# power.net
KiCad netlist of a schematic drawn in Altium Designer
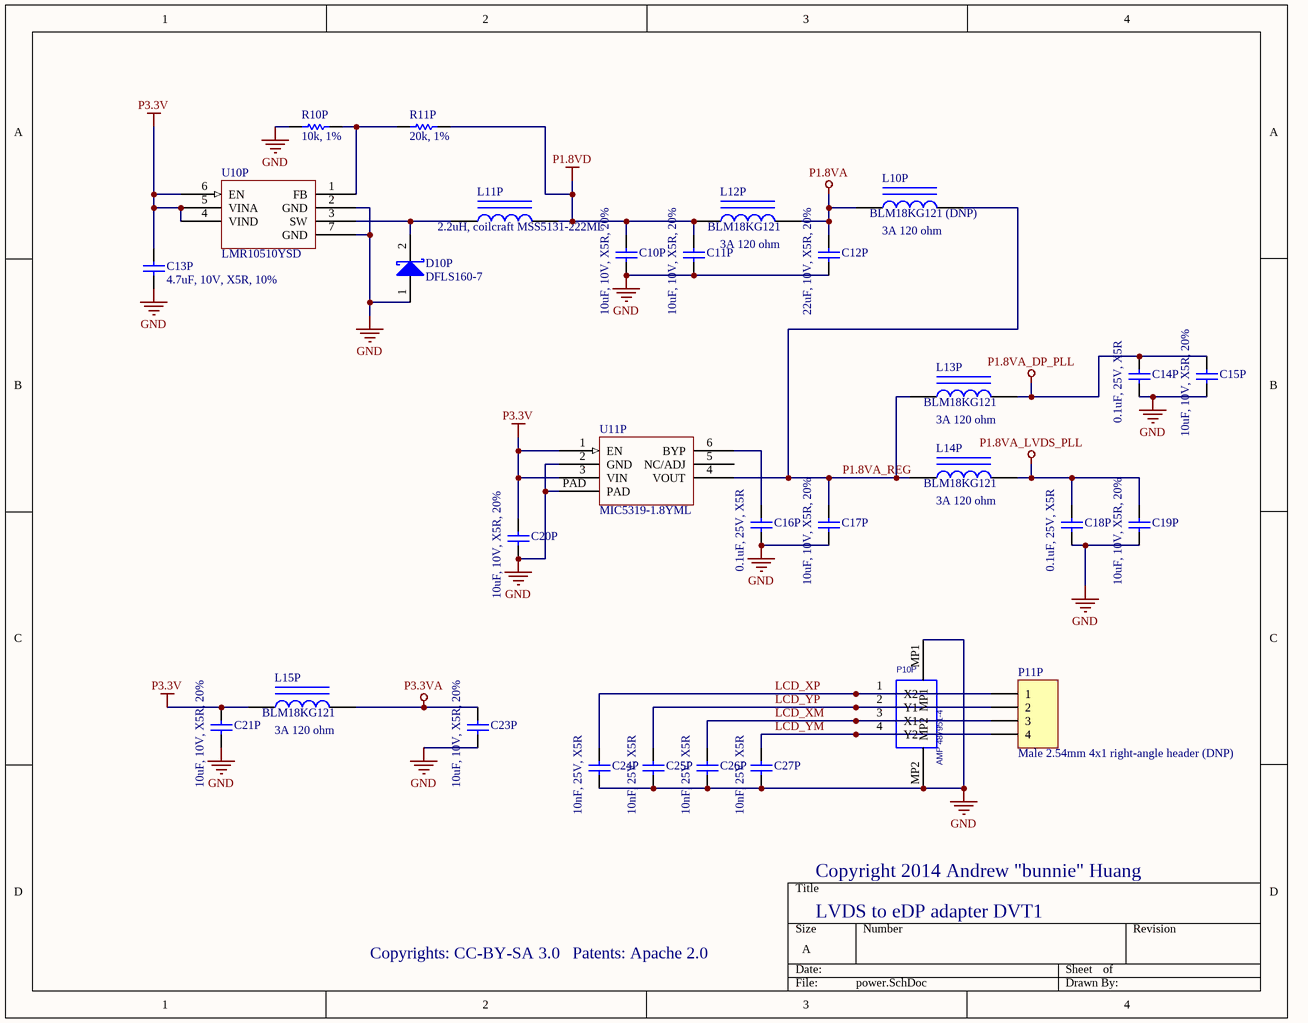
[diagram p0: power.SchDoc]

(export (version "E")
  (design (tool "Eeschema 10.0.6"))
  (components
    (comp (ref "C10P")
      (value "10uF, 10V, X5R, 20%")
      (footprint "CAPC1608N")
      (description "Capacitor (Semiconductor SIM Model)")
      (fields (field (name "PUBLISHER") "Altium Limited"))
      (libsource (lib "Miscellaneous Devices") (part "Cap Semi"))
    )
    (comp (ref "C11P")
      (value "10uF, 10V, X5R, 20%")
      (footprint "CAPC1608N")
      (description "Capacitor (Semiconductor SIM Model)")
      (fields (field (name "PUBLISHER") "Altium Limited"))
      (libsource (lib "Miscellaneous Devices") (part "Cap Semi"))
    )
    (comp (ref "C12P")
      (value "22uF, 10V, X5R, 20%")
      (footprint "CAPC2012N")
      (description "Capacitor (Semiconductor SIM Model)")
      (fields (field (name "PUBLISHER") "Altium Limited"))
      (libsource (lib "Miscellaneous Devices") (part "Cap Semi"))
    )
    (comp (ref "C13P")
      (value "4.7uF, 10V, X5R, 10%")
      (footprint "CAPC1608N")
      (description "Capacitor (Semiconductor SIM Model)")
      (fields (field (name "PUBLISHER") "Altium Limited"))
      (libsource (lib "Miscellaneous Devices") (part "Cap Semi"))
    )
    (comp (ref "C14P")
      (value "0.1uF, 25V, X5R")
      (footprint "CAPC1005N")
      (description "Capacitor (Semiconductor SIM Model)")
      (fields (field (name "PUBLISHER") "Altium Limited"))
      (libsource (lib "Miscellaneous Devices") (part "Cap Semi"))
    )
    (comp (ref "C15P")
      (value "10uF, 10V, X5R, 20%")
      (footprint "CAPC1608N")
      (description "Capacitor (Semiconductor SIM Model)")
      (fields (field (name "PUBLISHER") "Altium Limited"))
      (libsource (lib "Miscellaneous Devices") (part "Cap Semi"))
    )
    (comp (ref "C16P")
      (value "0.1uF, 25V, X5R")
      (footprint "CAPC1005N")
      (description "Capacitor (Semiconductor SIM Model)")
      (fields (field (name "PUBLISHER") "Altium Limited"))
      (libsource (lib "Miscellaneous Devices") (part "Cap Semi"))
    )
    (comp (ref "C17P")
      (value "10uF, 10V, X5R, 20%")
      (footprint "CAPC1608N")
      (description "Capacitor (Semiconductor SIM Model)")
      (fields (field (name "PUBLISHER") "Altium Limited"))
      (libsource (lib "Miscellaneous Devices") (part "Cap Semi"))
    )
    (comp (ref "C18P")
      (value "0.1uF, 25V, X5R")
      (footprint "CAPC1005N")
      (description "Capacitor (Semiconductor SIM Model)")
      (fields (field (name "PUBLISHER") "Altium Limited"))
      (libsource (lib "Miscellaneous Devices") (part "Cap Semi"))
    )
    (comp (ref "C19P")
      (value "10uF, 10V, X5R, 20%")
      (footprint "CAPC1608N")
      (description "Capacitor (Semiconductor SIM Model)")
      (fields (field (name "PUBLISHER") "Altium Limited"))
      (libsource (lib "Miscellaneous Devices") (part "Cap Semi"))
    )
    (comp (ref "C20P")
      (value "10uF, 10V, X5R, 20%")
      (footprint "CAPC1608N")
      (description "Capacitor (Semiconductor SIM Model)")
      (fields (field (name "PUBLISHER") "Altium Limited"))
      (libsource (lib "Miscellaneous Devices") (part "Cap Semi"))
    )
    (comp (ref "C21P")
      (value "10uF, 10V, X5R, 20%")
      (footprint "CAPC1608N")
      (description "Capacitor (Semiconductor SIM Model)")
      (fields (field (name "PUBLISHER") "Altium Limited"))
      (libsource (lib "Miscellaneous Devices") (part "Cap Semi"))
    )
    (comp (ref "C23P")
      (value "10uF, 10V, X5R, 20%")
      (footprint "CAPC1608N")
      (description "Capacitor (Semiconductor SIM Model)")
      (fields (field (name "PUBLISHER") "Altium Limited"))
      (libsource (lib "Miscellaneous Devices") (part "Cap Semi"))
    )
    (comp (ref "C24P")
      (value "10nF, 25V, X5R")
      (footprint "CAPC1005N")
      (description "Capacitor (Semiconductor SIM Model)")
      (fields (field (name "PUBLISHER") "Altium Limited"))
      (libsource (lib "Miscellaneous Devices") (part "Cap Semi"))
    )
    (comp (ref "C25P")
      (value "10nF, 25V, X5R")
      (footprint "CAPC1005N")
      (description "Capacitor (Semiconductor SIM Model)")
      (fields (field (name "PUBLISHER") "Altium Limited"))
      (libsource (lib "Miscellaneous Devices") (part "Cap Semi"))
    )
    (comp (ref "C26P")
      (value "10nF, 25V, X5R")
      (footprint "CAPC1005N")
      (description "Capacitor (Semiconductor SIM Model)")
      (fields (field (name "PUBLISHER") "Altium Limited"))
      (libsource (lib "Miscellaneous Devices") (part "Cap Semi"))
    )
    (comp (ref "C27P")
      (value "10nF, 25V, X5R")
      (footprint "CAPC1005N")
      (description "Capacitor (Semiconductor SIM Model)")
      (fields (field (name "PUBLISHER") "Altium Limited"))
      (libsource (lib "Miscellaneous Devices") (part "Cap Semi"))
    )
    (comp (ref "D10P")
      (value "DFLS160-7")
      (footprint "POWERDI-123")
      (description "Schottky Diode")
      (fields (field (name "PUBLISHER") "Altium Limited"))
      (libsource (lib "Miscellaneous Devices") (part "D Schottky"))
    )
    (comp (ref "L10P")
      (value "BLM18KG121 (DNP)")
      (footprint "INDC1608AN")
      (description "Magnetic-Core Inductor")
      (fields (field (name "ALTIUM_VALUE") "3A 120 ohm") (field (name "PUBLISHER") "Altium Limited"))
      (libsource (lib "Miscellaneous Devices") (part "Inductor Iron"))
    )
    (comp (ref "L11P")
      (value "2.2uH, coilcraft MSS5131-222ML")
      (footprint "COILCRAFT_MSS5121")
      (description "Magnetic-Core Inductor")
      (fields (field (name "PUBLISHER") "Altium Limited"))
      (libsource (lib "Miscellaneous Devices") (part "Inductor Iron"))
    )
    (comp (ref "L12P")
      (value "BLM18KG121")
      (footprint "INDC1608AN")
      (description "Magnetic-Core Inductor")
      (fields (field (name "ALTIUM_VALUE") "3A 120 ohm") (field (name "PUBLISHER") "Altium Limited"))
      (libsource (lib "Miscellaneous Devices") (part "Inductor Iron"))
    )
    (comp (ref "L13P")
      (value "BLM18KG121")
      (footprint "INDC1608AN")
      (description "Magnetic-Core Inductor")
      (fields (field (name "ALTIUM_VALUE") "3A 120 ohm") (field (name "PUBLISHER") "Altium Limited"))
      (libsource (lib "Miscellaneous Devices") (part "Inductor Iron"))
    )
    (comp (ref "L14P")
      (value "BLM18KG121")
      (footprint "INDC1608AN")
      (description "Magnetic-Core Inductor")
      (fields (field (name "ALTIUM_VALUE") "3A 120 ohm") (field (name "PUBLISHER") "Altium Limited"))
      (libsource (lib "Miscellaneous Devices") (part "Inductor Iron"))
    )
    (comp (ref "L15P")
      (value "BLM18KG121")
      (footprint "INDC1608AN")
      (description "Magnetic-Core Inductor")
      (fields (field (name "ALTIUM_VALUE") "3A 120 ohm") (field (name "PUBLISHER") "Altium Limited"))
      (libsource (lib "Miscellaneous Devices") (part "Inductor Iron"))
    )
    (comp (ref "P10P") (value "AMP 487951-4") (libsource (lib "*") (part "TFT_TP_CON")))
    (comp (ref "P11P")
      (value "Male 2.54mm 4x1 right-angle header (DNP)")
      (footprint "HDR1X4H")
      (description "Header, 4-Pin, Right Angle")
      (fields (field (name "PUBLISHER") "Altium Limited"))
      (libsource (lib "Miscellaneous Connectors") (part "Header 4H"))
    )
    (comp (ref "R10P")
      (value "10k, 1%")
      (footprint "RESC1005N")
      (description "Resistor")
      (fields (field (name "PUBLISHER") "Altium Limited"))
      (libsource (lib "Miscellaneous Devices") (part "Res1"))
    )
    (comp (ref "R11P")
      (value "20k, 1%")
      (footprint "RESC1005N")
      (description "Resistor")
      (fields (field (name "PUBLISHER") "Altium Limited"))
      (libsource (lib "Miscellaneous Devices") (part "Res1"))
    )
    (comp (ref "U10P")
      (value "LMR10510YSD")
      (footprint "SON95P300X300X80-7V")
      (description "NatSemi 1.5A step-down regulator in LLP")
      (libsource (lib "commonsch") (part "LMR10515XSD"))
    )
    (comp (ref "U11P")
      (value "MIC5319-1.8YML")
      (footprint "MICREL_MLF2x2_6")
      (description "500 mA uCap ultra-low dropout high PSRR LDO regulator")
      (libsource (lib "commonsch") (part "MIC5319-XXYML"))
    )
  )
  (nets
    (net (code "1") (name "/LCD_XM") (class "Default")
      (node (ref "C26P") (pin "2") (pinfunction "2_2") (pintype "passive"))
      (node (ref "P10P") (pin "3") (pinfunction "X1_3") (pintype "passive"))
      (node (ref "P11P") (pin "3") (pinfunction "3_3") (pintype "passive"))
    )
    (net (code "2") (name "/LCD_XP") (class "Default")
      (node (ref "C24P") (pin "2") (pinfunction "2_2") (pintype "passive"))
      (node (ref "P10P") (pin "1") (pinfunction "X2_1") (pintype "passive"))
      (node (ref "P11P") (pin "1") (pinfunction "1_1") (pintype "passive"))
    )
    (net (code "3") (name "/LCD_YM") (class "Default")
      (node (ref "C27P") (pin "2") (pinfunction "2_2") (pintype "passive"))
      (node (ref "P10P") (pin "4") (pinfunction "Y2_4") (pintype "passive"))
      (node (ref "P11P") (pin "4") (pinfunction "4_4") (pintype "passive"))
    )
    (net (code "4") (name "/LCD_YP") (class "Default")
      (node (ref "C25P") (pin "2") (pinfunction "2_2") (pintype "passive"))
      (node (ref "P10P") (pin "2") (pinfunction "Y1_2") (pintype "passive"))
      (node (ref "P11P") (pin "2") (pinfunction "2_2") (pintype "passive"))
    )
    (net (code "5") (name "/P1.8VA_REG") (class "Default")
      (node (ref "C17P") (pin "2") (pinfunction "2_2") (pintype "passive"))
      (node (ref "L10P") (pin "2") (pinfunction "2_2") (pintype "passive"))
      (node (ref "L13P") (pin "1") (pinfunction "1_1") (pintype "passive"))
      (node (ref "L14P") (pin "1") (pinfunction "1_1") (pintype "passive"))
      (node (ref "U11P") (pin "4") (pinfunction "VOUT_4") (pintype "power_in"))
    )
    (net (code "6") (name "GND") (class "Default")
      (node (ref "C10P") (pin "1") (pinfunction "1_1") (pintype "passive"))
      (node (ref "C11P") (pin "1") (pinfunction "1_1") (pintype "passive"))
      (node (ref "C12P") (pin "2") (pinfunction "2_2") (pintype "passive"))
      (node (ref "C13P") (pin "2") (pinfunction "2_2") (pintype "passive"))
      (node (ref "C14P") (pin "1") (pinfunction "1_1") (pintype "passive"))
      (node (ref "C15P") (pin "1") (pinfunction "1_1") (pintype "passive"))
      (node (ref "C16P") (pin "1") (pinfunction "1_1") (pintype "passive"))
      (node (ref "C17P") (pin "1") (pinfunction "1_1") (pintype "passive"))
      (node (ref "C18P") (pin "1") (pinfunction "1_1") (pintype "passive"))
      (node (ref "C19P") (pin "1") (pinfunction "1_1") (pintype "passive"))
      (node (ref "C20P") (pin "1") (pinfunction "1_1") (pintype "passive"))
      (node (ref "C21P") (pin "1") (pinfunction "1_1") (pintype "passive"))
      (node (ref "C23P") (pin "1") (pinfunction "1_1") (pintype "passive"))
      (node (ref "C24P") (pin "1") (pinfunction "1_1") (pintype "passive"))
      (node (ref "C25P") (pin "1") (pinfunction "1_1") (pintype "passive"))
      (node (ref "C26P") (pin "1") (pinfunction "1_1") (pintype "passive"))
      (node (ref "C27P") (pin "1") (pinfunction "1_1") (pintype "passive"))
      (node (ref "D10P") (pin "1") (pinfunction "A_1") (pintype "passive"))
      (node (ref "P10P") (pin "MP1") (pinfunction "MP1_MP1") (pintype "passive"))
      (node (ref "P10P") (pin "MP2") (pinfunction "MP2_MP2") (pintype "passive"))
      (node (ref "R10P") (pin "2") (pinfunction "2_2") (pintype "passive"))
      (node (ref "U10P") (pin "2") (pinfunction "GND_2") (pintype "power_in"))
      (node (ref "U10P") (pin "7") (pinfunction "GND_7") (pintype "power_in"))
      (node (ref "U11P") (pin "2") (pinfunction "GND_2") (pintype "power_in"))
      (node (ref "U11P") (pin "PAD") (pinfunction "PAD_PAD") (pintype "passive"))
    )
    (net (code "7") (name "Net-(D10P-K)") (class "Default")
      (node (ref "D10P") (pin "2") (pinfunction "K_2") (pintype "passive"))
      (node (ref "L11P") (pin "1") (pinfunction "1_1") (pintype "passive"))
      (node (ref "U10P") (pin "3") (pinfunction "SW_3") (pintype "passive"))
    )
    (net (code "8") (name "Net-(U10P-FB)") (class "Default")
      (node (ref "R10P") (pin "1") (pinfunction "1_1") (pintype "passive"))
      (node (ref "R11P") (pin "2") (pinfunction "2_2") (pintype "passive"))
      (node (ref "U10P") (pin "1") (pinfunction "FB_1") (pintype "passive"))
    )
    (net (code "9") (name "Net-(U11P-BYP)") (class "Default")
      (node (ref "C16P") (pin "2") (pinfunction "2_2") (pintype "passive"))
      (node (ref "U11P") (pin "6") (pinfunction "BYP_6") (pintype "passive"))
    )
    (net (code "10") (name "P1.8VA") (class "Default")
      (node (ref "C12P") (pin "1") (pinfunction "1_1") (pintype "passive"))
      (node (ref "L10P") (pin "1") (pinfunction "1_1") (pintype "passive"))
      (node (ref "L12P") (pin "2") (pinfunction "2_2") (pintype "passive"))
    )
    (net (code "11") (name "P1.8VA_DP_PLL") (class "Default")
      (node (ref "C14P") (pin "2") (pinfunction "2_2") (pintype "passive"))
      (node (ref "C15P") (pin "2") (pinfunction "2_2") (pintype "passive"))
      (node (ref "L13P") (pin "2") (pinfunction "2_2") (pintype "passive"))
    )
    (net (code "12") (name "P1.8VA_LVDS_PLL") (class "Default")
      (node (ref "C18P") (pin "2") (pinfunction "2_2") (pintype "passive"))
      (node (ref "C19P") (pin "2") (pinfunction "2_2") (pintype "passive"))
      (node (ref "L14P") (pin "2") (pinfunction "2_2") (pintype "passive"))
    )
    (net (code "13") (name "P1.8VD") (class "Default")
      (node (ref "C10P") (pin "2") (pinfunction "2_2") (pintype "passive"))
      (node (ref "C11P") (pin "2") (pinfunction "2_2") (pintype "passive"))
      (node (ref "L11P") (pin "2") (pinfunction "2_2") (pintype "passive"))
      (node (ref "L12P") (pin "1") (pinfunction "1_1") (pintype "passive"))
      (node (ref "R11P") (pin "1") (pinfunction "1_1") (pintype "passive"))
    )
    (net (code "14") (name "P3.3V") (class "Default")
      (node (ref "C13P") (pin "1") (pinfunction "1_1") (pintype "passive"))
      (node (ref "C20P") (pin "2") (pinfunction "2_2") (pintype "passive"))
      (node (ref "C21P") (pin "2") (pinfunction "2_2") (pintype "passive"))
      (node (ref "L15P") (pin "1") (pinfunction "1_1") (pintype "passive"))
      (node (ref "U10P") (pin "4") (pinfunction "VIND_4") (pintype "power_in"))
      (node (ref "U10P") (pin "5") (pinfunction "VINA_5") (pintype "power_in"))
      (node (ref "U10P") (pin "6") (pinfunction "EN_6") (pintype "input"))
      (node (ref "U11P") (pin "1") (pinfunction "EN_1") (pintype "input"))
      (node (ref "U11P") (pin "3") (pinfunction "VIN_3") (pintype "power_in"))
    )
    (net (code "15") (name "P3.3VA") (class "Default")
      (node (ref "C23P") (pin "2") (pinfunction "2_2") (pintype "passive"))
      (node (ref "L15P") (pin "2") (pinfunction "2_2") (pintype "passive"))
    )
    (net (code "16") (name "unconnected-(U11P-NC{slash}ADJ-Pad5)") (class "Default")
      (node (ref "U11P") (pin "5") (pinfunction "NC/ADJ_5") (pintype "passive"))
    )
  )
)
